# crocopoi-v1_5.net
KiCad netlist of a schematic drawn in EAGLE
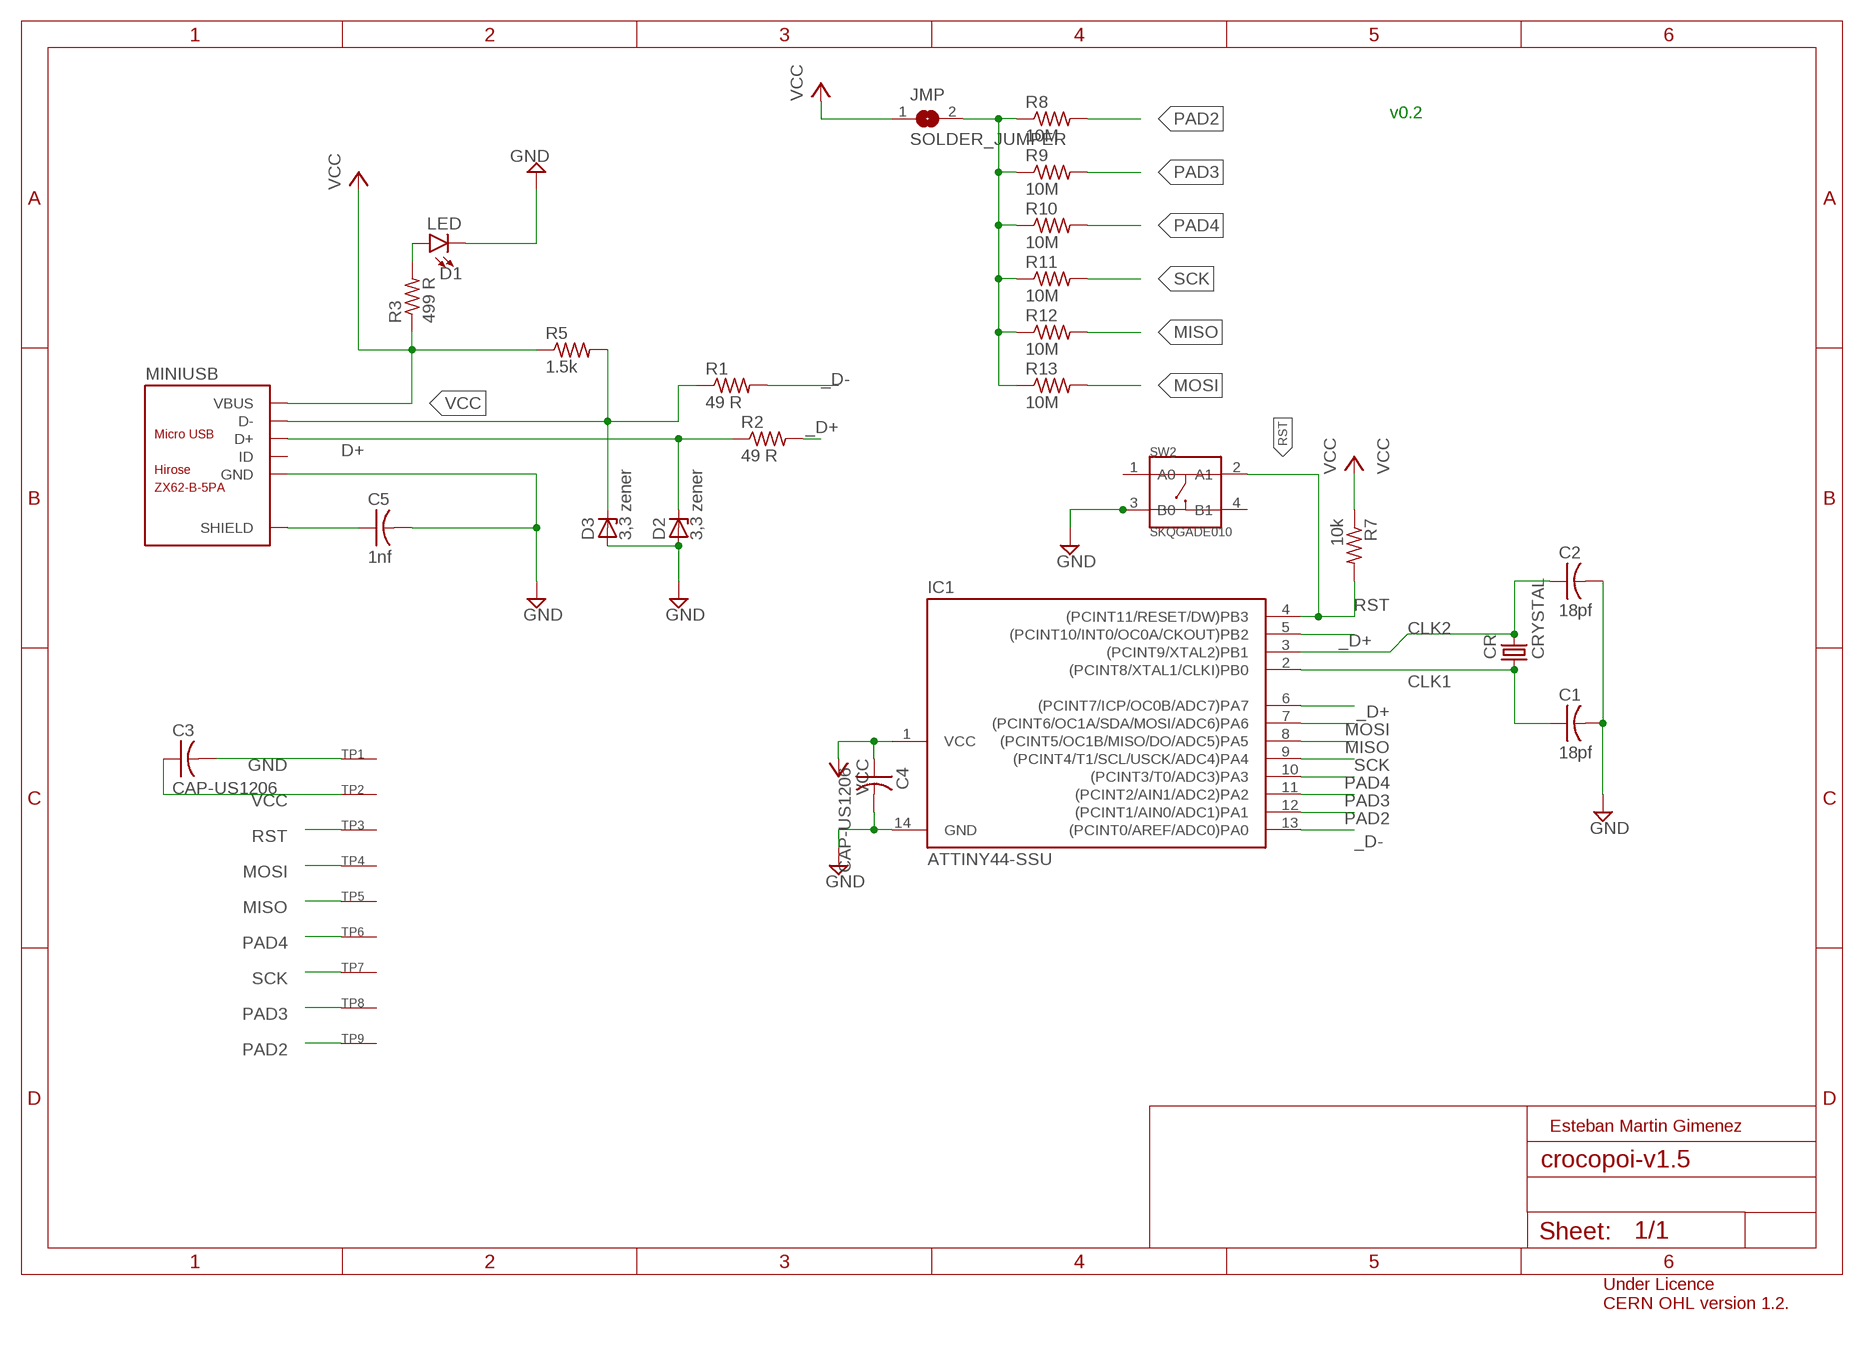
[diagram p0: schematic, sheet 1]

(export (version "E")
  (design (tool "Eeschema 10.0.6"))
  (components
    (comp (ref "C1")
      (value "18pf")
      (footprint "eagle-import:C1206FAB")
      (libsource (lib "eagle-import") (part "CAP-US1206FAB"))
    )
    (comp (ref "C2")
      (value "18pf")
      (footprint "eagle-import:C1206FAB")
      (libsource (lib "eagle-import") (part "CAP-US1206FAB"))
    )
    (comp (ref "C3")
      (value "CAP-US1206")
      (footprint "eagle-import:C1206")
      (libsource (lib "eagle-import") (part "CAP-US1206"))
    )
    (comp (ref "C4")
      (value "CAP-US1206")
      (footprint "eagle-import:C1206")
      (libsource (lib "eagle-import") (part "CAP-US1206"))
    )
    (comp (ref "C5")
      (value "1nf")
      (footprint "eagle-import:C1206FAB")
      (libsource (lib "eagle-import") (part "CAP-US1206FAB"))
    )
    (comp (ref "CR")
      (value "CRYSTAL")
      (footprint "eagle-import:2-SMD-5X3MM")
      (libsource (lib "eagle-import") (part "CRYSTAL"))
    )
    (comp (ref "D1")
      (value "LED")
      (footprint "eagle-import:LED-1206")
      (libsource (lib "eagle-import") (part "LED1206"))
    )
    (comp (ref "D2")
      (value "3,3 zener")
      (footprint "eagle-import:SOD123")
      (libsource (lib "eagle-import") (part "ZENER_DIODESOD123"))
    )
    (comp (ref "D3")
      (value "3,3 zener")
      (footprint "eagle-import:SOD123")
      (libsource (lib "eagle-import") (part "ZENER_DIODESOD123"))
    )
    (comp (ref "IC1")
      (value "ATTINY44-SSU")
      (footprint "eagle-import:SOIC14")
      (libsource (lib "eagle-import") (part "ATTINY44-SSU"))
    )
    (comp (ref "JMP")
      (value "SOLDER_JUMPER")
      (footprint "eagle-import:SJFAB")
      (libsource (lib "eagle-import") (part "SOLDER_JUMPER"))
    )
    (comp (ref "MINIUSB")
      (value "ZX62-B-5PA")
      (footprint "eagle-import:MICRO-USB5+6P-SMD-0.65-AB")
      (libsource (lib "eagle-import") (part "MICRO-USB-SMD(ZX62-B-5PA)"))
    )
    (comp (ref "R1")
      (value "49 R")
      (footprint "eagle-import:R1206FAB")
      (libsource (lib "eagle-import") (part "RES-US1206FAB"))
    )
    (comp (ref "R2")
      (value "49 R")
      (footprint "eagle-import:R1206FAB")
      (libsource (lib "eagle-import") (part "RES-US1206FAB"))
    )
    (comp (ref "R3")
      (value "499 R")
      (footprint "eagle-import:R1206FAB")
      (libsource (lib "eagle-import") (part "RES-US1206FAB"))
    )
    (comp (ref "R5")
      (value "1.5k")
      (footprint "eagle-import:R1206FAB")
      (libsource (lib "eagle-import") (part "RES-US1206FAB"))
    )
    (comp (ref "R7")
      (value "10k")
      (footprint "eagle-import:R1206FAB")
      (libsource (lib "eagle-import") (part "RES-US1206FAB"))
    )
    (comp (ref "R8")
      (value "10M")
      (footprint "eagle-import:R1206FAB")
      (libsource (lib "eagle-import") (part "RES-US1206FAB"))
    )
    (comp (ref "R9")
      (value "10M")
      (footprint "eagle-import:R1206FAB")
      (libsource (lib "eagle-import") (part "RES-US1206FAB"))
    )
    (comp (ref "R10")
      (value "10M")
      (footprint "eagle-import:R1206FAB")
      (libsource (lib "eagle-import") (part "RES-US1206FAB"))
    )
    (comp (ref "R11")
      (value "10M")
      (footprint "eagle-import:R1206FAB")
      (libsource (lib "eagle-import") (part "RES-US1206FAB"))
    )
    (comp (ref "R12")
      (value "10M")
      (footprint "eagle-import:R1206FAB")
      (libsource (lib "eagle-import") (part "RES-US1206FAB"))
    )
    (comp (ref "R13")
      (value "10M")
      (footprint "eagle-import:R1206FAB")
      (libsource (lib "eagle-import") (part "RES-US1206FAB"))
    )
    (comp (ref "SW2")
      (value "SKQGADE010")
      (footprint "eagle-import:SW4-SMD-5.2X5.2X1.5MM")
      (libsource (lib "eagle-import") (part "SMD-BUTTON(4P-5.2X5.2X1.5MM-SKQGADE010)-SKQGADE010"))
    )
    (comp (ref "TP1")
      (value "SEWTAPBIG")
      (footprint "eagle-import:BIGTAP")
      (libsource (lib "eagle-import") (part "SEWTAPBIG"))
    )
    (comp (ref "TP2")
      (value "SEWTAPBIG")
      (footprint "eagle-import:BIGTAP")
      (libsource (lib "eagle-import") (part "SEWTAPBIG"))
    )
    (comp (ref "TP3")
      (value "SEWTAPBIG")
      (footprint "eagle-import:BIGTAP")
      (libsource (lib "eagle-import") (part "SEWTAPBIG"))
    )
    (comp (ref "TP4")
      (value "SEWTAPBIG")
      (footprint "eagle-import:BIGTAP")
      (libsource (lib "eagle-import") (part "SEWTAPBIG"))
    )
    (comp (ref "TP5")
      (value "SEWTAPBIG")
      (footprint "eagle-import:BIGTAP")
      (libsource (lib "eagle-import") (part "SEWTAPBIG"))
    )
    (comp (ref "TP6")
      (value "SEWTAPBIG")
      (footprint "eagle-import:BIGTAP")
      (libsource (lib "eagle-import") (part "SEWTAPBIG"))
    )
    (comp (ref "TP7")
      (value "SEWTAPBIG")
      (footprint "eagle-import:BIGTAP")
      (libsource (lib "eagle-import") (part "SEWTAPBIG"))
    )
    (comp (ref "TP8")
      (value "SEWTAPBIG")
      (footprint "eagle-import:BIGTAP")
      (libsource (lib "eagle-import") (part "SEWTAPBIG"))
    )
    (comp (ref "TP9")
      (value "SEWTAPBIG")
      (footprint "eagle-import:BIGTAP")
      (libsource (lib "eagle-import") (part "SEWTAPBIG"))
    )
  )
  (nets
    (net (code "1") (name "/CLK1") (class "Default")
      (node (ref "C1") (pin "1") (pinfunction "1_1") (pintype "passive"))
      (node (ref "CR") (pin "P$1") (pinfunction "1_P$1") (pintype "passive"))
      (node (ref "IC1") (pin "2") (pinfunction "(PCINT8/XTAL1/CLKI)PB0_2") (pintype "bidirectional"))
    )
    (net (code "2") (name "/CLK2") (class "Default")
      (node (ref "C2") (pin "1") (pinfunction "1_1") (pintype "passive"))
      (node (ref "CR") (pin "P$2") (pinfunction "2_P$2") (pintype "passive"))
      (node (ref "IC1") (pin "3") (pinfunction "(PCINT9/XTAL2)PB1_3") (pintype "bidirectional"))
    )
    (net (code "3") (name "/D+") (class "Default")
      (node (ref "D2") (pin "CATHODE") (pinfunction "CATHODE_CATHODE") (pintype "passive"))
      (node (ref "MINIUSB") (pin "3") (pinfunction "D+_3") (pintype "bidirectional"))
      (node (ref "R2") (pin "1") (pinfunction "1_1") (pintype "passive"))
    )
    (net (code "4") (name "/_D+") (class "Default")
      (node (ref "IC1") (pin "5") (pinfunction "(PCINT10/INT0/OC0A/CKOUT)PB2_5") (pintype "bidirectional"))
      (node (ref "IC1") (pin "6") (pinfunction "(PCINT7/ICP/OC0B/ADC7)PA7_6") (pintype "bidirectional"))
      (node (ref "R2") (pin "2") (pinfunction "2_2") (pintype "passive"))
    )
    (net (code "5") (name "/_D-") (class "Default")
      (node (ref "IC1") (pin "13") (pinfunction "(PCINT0/AREF/ADC0)PA0_13") (pintype "bidirectional"))
      (node (ref "R1") (pin "2") (pinfunction "2_2") (pintype "passive"))
    )
    (net (code "6") (name "GND") (class "Default")
      (node (ref "C1") (pin "2") (pinfunction "2_2") (pintype "passive"))
      (node (ref "C2") (pin "2") (pinfunction "2_2") (pintype "passive"))
      (node (ref "C3") (pin "2") (pinfunction "2_2") (pintype "passive"))
      (node (ref "C4") (pin "2") (pinfunction "2_2") (pintype "passive"))
      (node (ref "C5") (pin "2") (pinfunction "2_2") (pintype "passive"))
      (node (ref "D1") (pin "C") (pinfunction "C_C") (pintype "passive"))
      (node (ref "D2") (pin "ANODE") (pinfunction "ANODE_ANODE") (pintype "passive"))
      (node (ref "D3") (pin "ANODE") (pinfunction "ANODE_ANODE") (pintype "passive"))
      (node (ref "IC1") (pin "14") (pinfunction "GND_14") (pintype "power_in"))
      (node (ref "MINIUSB") (pin "5") (pinfunction "GND_5") (pintype "power_in"))
      (node (ref "SW2") (pin "3") (pinfunction "B0_3") (pintype "bidirectional"))
      (node (ref "TP1") (pin "P$1") (pinfunction "SEW_P$1") (pintype "bidirectional"))
    )
    (net (code "7") (name "MISO") (class "Default")
      (node (ref "IC1") (pin "8") (pinfunction "(PCINT5/OC1B/MISO/DO/ADC5)PA5_8") (pintype "bidirectional"))
      (node (ref "R12") (pin "2") (pinfunction "2_2") (pintype "passive"))
      (node (ref "TP5") (pin "P$1") (pinfunction "SEW_P$1") (pintype "bidirectional"))
    )
    (net (code "8") (name "MOSI") (class "Default")
      (node (ref "IC1") (pin "7") (pinfunction "(PCINT6/OC1A/SDA/MOSI/ADC6)PA6_7") (pintype "bidirectional"))
      (node (ref "R13") (pin "2") (pinfunction "2_2") (pintype "passive"))
      (node (ref "TP4") (pin "P$1") (pinfunction "SEW_P$1") (pintype "bidirectional"))
    )
    (net (code "9") (name "Net-(C5-Pad1)") (class "Default")
      (node (ref "C5") (pin "1") (pinfunction "1_1") (pintype "passive"))
      (node (ref "MINIUSB") (pin "P1") (pinfunction "SHIELD_P1") (pintype "power_in"))
      (node (ref "MINIUSB") (pin "P2") (pinfunction "SHIELD_P2") (pintype "power_in"))
      (node (ref "MINIUSB") (pin "P3") (pinfunction "SHIELD_P3") (pintype "power_in"))
      (node (ref "MINIUSB") (pin "P4") (pinfunction "SHIELD_P4") (pintype "power_in"))
      (node (ref "MINIUSB") (pin "P5") (pinfunction "SHIELD_P5") (pintype "power_in"))
      (node (ref "MINIUSB") (pin "P6") (pinfunction "SHIELD_P6") (pintype "power_in"))
    )
    (net (code "10") (name "Net-(D1-PadA)") (class "Default")
      (node (ref "D1") (pin "A") (pinfunction "A_A") (pintype "passive"))
      (node (ref "R3") (pin "2") (pinfunction "2_2") (pintype "passive"))
    )
    (net (code "11") (name "Net-(JMP-Pad2)") (class "Default")
      (node (ref "JMP") (pin "2") (pinfunction "2_2") (pintype "passive"))
      (node (ref "R10") (pin "1") (pinfunction "1_1") (pintype "passive"))
      (node (ref "R11") (pin "1") (pinfunction "1_1") (pintype "passive"))
      (node (ref "R12") (pin "1") (pinfunction "1_1") (pintype "passive"))
      (node (ref "R13") (pin "1") (pinfunction "1_1") (pintype "passive"))
      (node (ref "R8") (pin "1") (pinfunction "1_1") (pintype "passive"))
      (node (ref "R9") (pin "1") (pinfunction "1_1") (pintype "passive"))
    )
    (net (code "12") (name "Net-(MINIUSB-D-)") (class "Default")
      (node (ref "D3") (pin "CATHODE") (pinfunction "CATHODE_CATHODE") (pintype "passive"))
      (node (ref "MINIUSB") (pin "2") (pinfunction "D-_2") (pintype "bidirectional"))
      (node (ref "R1") (pin "1") (pinfunction "1_1") (pintype "passive"))
      (node (ref "R5") (pin "2") (pinfunction "2_2") (pintype "passive"))
    )
    (net (code "13") (name "PAD2") (class "Default")
      (node (ref "IC1") (pin "12") (pinfunction "(PCINT1/AIN0/ADC1)PA1_12") (pintype "bidirectional"))
      (node (ref "R8") (pin "2") (pinfunction "2_2") (pintype "passive"))
      (node (ref "TP9") (pin "P$1") (pinfunction "SEW_P$1") (pintype "bidirectional"))
    )
    (net (code "14") (name "PAD3") (class "Default")
      (node (ref "IC1") (pin "11") (pinfunction "(PCINT2/AIN1/ADC2)PA2_11") (pintype "bidirectional"))
      (node (ref "R9") (pin "2") (pinfunction "2_2") (pintype "passive"))
      (node (ref "TP8") (pin "P$1") (pinfunction "SEW_P$1") (pintype "bidirectional"))
    )
    (net (code "15") (name "PAD4") (class "Default")
      (node (ref "IC1") (pin "10") (pinfunction "(PCINT3/T0/ADC3)PA3_10") (pintype "bidirectional"))
      (node (ref "R10") (pin "2") (pinfunction "2_2") (pintype "passive"))
      (node (ref "TP6") (pin "P$1") (pinfunction "SEW_P$1") (pintype "bidirectional"))
    )
    (net (code "16") (name "RST") (class "Default")
      (node (ref "IC1") (pin "4") (pinfunction "(PCINT11/RESET/DW)PB3_4") (pintype "bidirectional"))
      (node (ref "R7") (pin "2") (pinfunction "2_2") (pintype "passive"))
      (node (ref "SW2") (pin "2") (pinfunction "A1_2") (pintype "bidirectional"))
      (node (ref "TP3") (pin "P$1") (pinfunction "SEW_P$1") (pintype "bidirectional"))
    )
    (net (code "17") (name "SCK") (class "Default")
      (node (ref "IC1") (pin "9") (pinfunction "(PCINT4/T1/SCL/USCK/ADC4)PA4_9") (pintype "bidirectional"))
      (node (ref "R11") (pin "2") (pinfunction "2_2") (pintype "passive"))
      (node (ref "TP7") (pin "P$1") (pinfunction "SEW_P$1") (pintype "bidirectional"))
    )
    (net (code "18") (name "VCC") (class "Default")
      (node (ref "C3") (pin "1") (pinfunction "1_1") (pintype "passive"))
      (node (ref "C4") (pin "1") (pinfunction "1_1") (pintype "passive"))
      (node (ref "IC1") (pin "1") (pinfunction "VCC_1") (pintype "power_in"))
      (node (ref "JMP") (pin "1") (pinfunction "1_1") (pintype "passive"))
      (node (ref "MINIUSB") (pin "1") (pinfunction "VBUS_1") (pintype "power_in"))
      (node (ref "R3") (pin "1") (pinfunction "1_1") (pintype "passive"))
      (node (ref "R5") (pin "1") (pinfunction "1_1") (pintype "passive"))
      (node (ref "R7") (pin "1") (pinfunction "1_1") (pintype "passive"))
      (node (ref "TP2") (pin "P$1") (pinfunction "SEW_P$1") (pintype "bidirectional"))
    )
    (net (code "19") (name "unconnected-(MINIUSB-ID-Pad4)") (class "Default")
      (node (ref "MINIUSB") (pin "4") (pinfunction "ID_4") (pintype "bidirectional"))
    )
    (net (code "20") (name "unconnected-(SW2-A0-Pad1)") (class "Default")
      (node (ref "SW2") (pin "1") (pinfunction "A0_1") (pintype "bidirectional"))
    )
    (net (code "21") (name "unconnected-(SW2-B1-Pad4)") (class "Default")
      (node (ref "SW2") (pin "4") (pinfunction "B1_4") (pintype "bidirectional"))
    )
  )
)
